# serial-io.net
KiCad netlist of a schematic drawn in Altium Designer
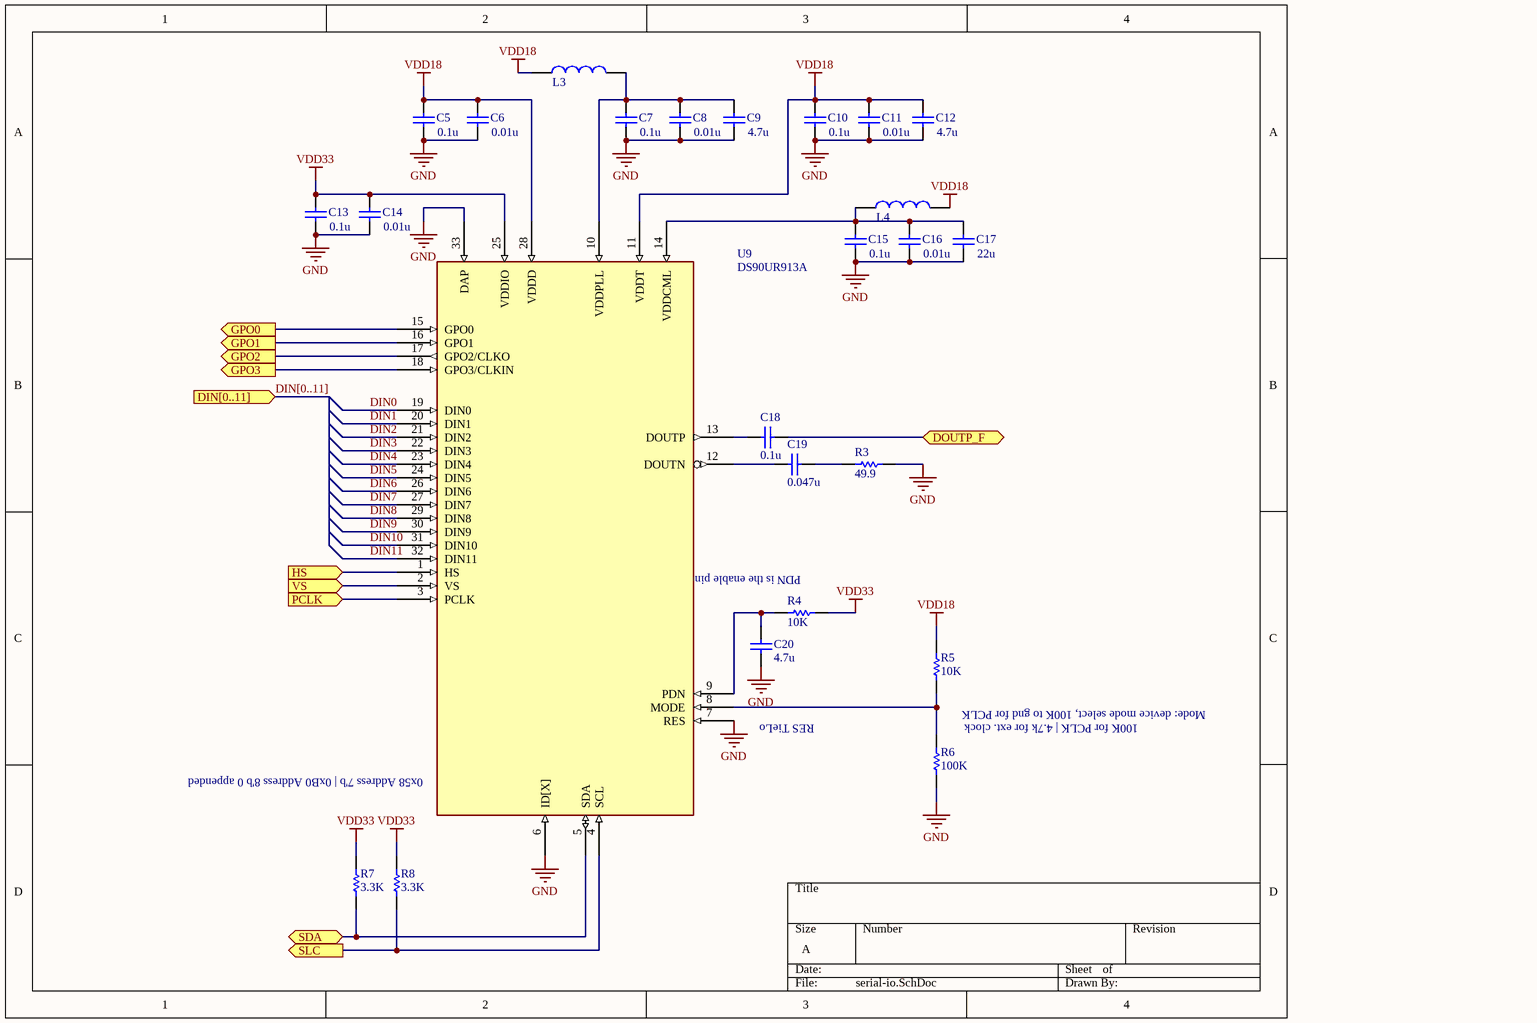
[diagram p0: serial-io.SchDoc]

(export (version "E")
  (design (tool "Eeschema 10.0.6"))
  (components
    (comp (ref "C5")
      (value "0.1u")
      (footprint "Cap_0402")
      (description "Capacitor")
      (fields (field (name "Comment") "X7R Ceramic") (field (name "PUBLISHER") "Altium Limited"))
      (libsource (lib "Miscellaneous Devices") (part "Cap"))
    )
    (comp (ref "C6")
      (value "0.01u")
      (footprint "Cap_0402")
      (description "Capacitor")
      (fields (field (name "Comment") "X7R Ceramic") (field (name "PUBLISHER") "Altium Limited"))
      (libsource (lib "Miscellaneous Devices") (part "Cap"))
    )
    (comp (ref "C7")
      (value "0.1u")
      (footprint "Cap_0402")
      (description "Capacitor")
      (fields (field (name "Comment") "X7R Ceramic") (field (name "PUBLISHER") "Altium Limited"))
      (libsource (lib "Miscellaneous Devices") (part "Cap"))
    )
    (comp (ref "C8")
      (value "0.01u")
      (footprint "Cap_0402")
      (description "Capacitor")
      (fields (field (name "Comment") "X7R Ceramic") (field (name "PUBLISHER") "Altium Limited"))
      (libsource (lib "Miscellaneous Devices") (part "Cap"))
    )
    (comp (ref "C9")
      (value "4.7u")
      (footprint "Cap_0402")
      (description "Capacitor")
      (fields (field (name "Comment") "X7R Ceramic") (field (name "PUBLISHER") "Altium Limited"))
      (libsource (lib "Miscellaneous Devices") (part "Cap"))
    )
    (comp (ref "C10")
      (value "0.1u")
      (footprint "Cap_0402")
      (description "Capacitor")
      (fields (field (name "Comment") "X7R Ceramic") (field (name "PUBLISHER") "Altium Limited"))
      (libsource (lib "Miscellaneous Devices") (part "Cap"))
    )
    (comp (ref "C11")
      (value "0.01u")
      (footprint "Cap_0402")
      (description "Capacitor")
      (fields (field (name "Comment") "X7R Ceramic") (field (name "PUBLISHER") "Altium Limited"))
      (libsource (lib "Miscellaneous Devices") (part "Cap"))
    )
    (comp (ref "C12")
      (value "4.7u")
      (footprint "Cap_0402")
      (description "Capacitor")
      (fields (field (name "Comment") "X7R Ceramic") (field (name "PUBLISHER") "Altium Limited"))
      (libsource (lib "Miscellaneous Devices") (part "Cap"))
    )
    (comp (ref "C13")
      (value "0.1u")
      (footprint "Cap_0402")
      (description "Capacitor")
      (fields (field (name "Comment") "X7R Ceramic") (field (name "PUBLISHER") "Altium Limited"))
      (libsource (lib "Miscellaneous Devices") (part "Cap"))
    )
    (comp (ref "C14")
      (value "0.01u")
      (footprint "Cap_0402")
      (description "Capacitor")
      (fields (field (name "Comment") "X7R Ceramic") (field (name "PUBLISHER") "Altium Limited"))
      (libsource (lib "Miscellaneous Devices") (part "Cap"))
    )
    (comp (ref "C15")
      (value "0.1u")
      (footprint "Cap_0402")
      (description "Capacitor")
      (fields (field (name "Comment") "X7R Ceramic") (field (name "PUBLISHER") "Altium Limited"))
      (libsource (lib "Miscellaneous Devices") (part "Cap"))
    )
    (comp (ref "C16")
      (value "0.01u")
      (footprint "Cap_0402")
      (description "Capacitor")
      (fields (field (name "Comment") "X7R Ceramic") (field (name "PUBLISHER") "Altium Limited"))
      (libsource (lib "Miscellaneous Devices") (part "Cap"))
    )
    (comp (ref "C17")
      (value "22u")
      (footprint "Cap-0603")
      (description "Capacitor")
      (fields (field (name "Comment") "X7R Ceramic") (field (name "PUBLISHER") "Altium Limited"))
      (libsource (lib "Miscellaneous Devices") (part "Cap"))
    )
    (comp (ref "C18")
      (value "0.1u")
      (footprint "Cap_0402")
      (description "Capacitor")
      (fields (field (name "Comment") "X7R Ceramic") (field (name "PUBLISHER") "Altium Limited"))
      (libsource (lib "Miscellaneous Devices") (part "Cap"))
    )
    (comp (ref "C19")
      (value "0.047u")
      (footprint "Cap_0402")
      (description "Capacitor")
      (fields (field (name "Comment") "X7R Ceramic") (field (name "PUBLISHER") "Altium Limited"))
      (libsource (lib "Miscellaneous Devices") (part "Cap"))
    )
    (comp (ref "C20")
      (value "4.7u")
      (footprint "Cap_0402")
      (description "Capacitor")
      (fields (field (name "Comment") "X7R Ceramic") (field (name "PUBLISHER") "Altium Limited"))
      (libsource (lib "Miscellaneous Devices") (part "Cap"))
    )
    (comp (ref "L3")
      (value "Ferrite Bead")
      (footprint "BLM18KG601SN1D")
      (libsource (lib "DA_Component_Library") (part "Ferrite Bead"))
    )
    (comp (ref "L4")
      (value "Ferrite Bead")
      (footprint "BLM18KG601SN1D")
      (libsource (lib "DA_Component_Library") (part "Ferrite Bead"))
    )
    (comp (ref "R3")
      (value "49.9")
      (footprint "Res_0402")
      (description "Resistor")
      (fields (field (name "Comment") "Res1") (field (name "PUBLISHER") "Altium Limited"))
      (libsource (lib "Miscellaneous Devices") (part "Res1"))
    )
    (comp (ref "R4")
      (value "10K")
      (footprint "Res_0402")
      (description "Resistor")
      (fields (field (name "Comment") "Res1") (field (name "PUBLISHER") "Altium Limited"))
      (libsource (lib "Miscellaneous Devices") (part "Res1"))
    )
    (comp (ref "R5")
      (value "10K")
      (footprint "Res_0402")
      (description "Resistor")
      (fields (field (name "Comment") "Res1") (field (name "PUBLISHER") "Altium Limited"))
      (libsource (lib "Miscellaneous Devices") (part "Res1"))
    )
    (comp (ref "R6")
      (value "100K")
      (footprint "Res_0402")
      (description "Resistor")
      (fields (field (name "Comment") "Res1") (field (name "PUBLISHER") "Altium Limited"))
      (libsource (lib "Miscellaneous Devices") (part "Res1"))
    )
    (comp (ref "R7")
      (value "3.3K")
      (footprint "Res_0402")
      (description "Resistor")
      (fields (field (name "Comment") "Res1") (field (name "PUBLISHER") "Altium Limited"))
      (libsource (lib "Miscellaneous Devices") (part "Res1"))
    )
    (comp (ref "R8")
      (value "3.3K")
      (footprint "Res_0402")
      (description "Resistor")
      (fields (field (name "Comment") "Res1") (field (name "PUBLISHER") "Altium Limited"))
      (libsource (lib "Miscellaneous Devices") (part "Res1"))
    )
    (comp (ref "U9")
      (value "DS90UR913A")
      (footprint "WQFN32-DS90UB913A")
      (description "DS90UR913ASERIALIZER")
      (libsource (lib "DA_Component_Library") (part "DS90UR913A"))
    )
  )
  (nets
    (net (code "1") (name "/DIN0") (class "Default")
      (node (ref "U9") (pin "19") (pinfunction "DIN0_19") (pintype "input"))
    )
    (net (code "2") (name "/DIN1") (class "Default")
      (node (ref "U9") (pin "20") (pinfunction "DIN1_20") (pintype "input"))
    )
    (net (code "3") (name "/DIN2") (class "Default")
      (node (ref "U9") (pin "21") (pinfunction "DIN2_21") (pintype "input"))
    )
    (net (code "4") (name "/DIN3") (class "Default")
      (node (ref "U9") (pin "22") (pinfunction "DIN3_22") (pintype "input"))
    )
    (net (code "5") (name "/DIN4") (class "Default")
      (node (ref "U9") (pin "23") (pinfunction "DIN4_23") (pintype "input"))
    )
    (net (code "6") (name "/DIN5") (class "Default")
      (node (ref "U9") (pin "24") (pinfunction "DIN5_24") (pintype "input"))
    )
    (net (code "7") (name "/DIN6") (class "Default")
      (node (ref "U9") (pin "26") (pinfunction "DIN6_26") (pintype "input"))
    )
    (net (code "8") (name "/DIN7") (class "Default")
      (node (ref "U9") (pin "27") (pinfunction "DIN7_27") (pintype "input"))
    )
    (net (code "9") (name "/DIN8") (class "Default")
      (node (ref "U9") (pin "29") (pinfunction "DIN8_29") (pintype "input"))
    )
    (net (code "10") (name "/DIN9") (class "Default")
      (node (ref "U9") (pin "30") (pinfunction "DIN9_30") (pintype "input"))
    )
    (net (code "11") (name "/DIN10") (class "Default")
      (node (ref "U9") (pin "31") (pinfunction "DIN10_31") (pintype "input"))
    )
    (net (code "12") (name "/DIN11") (class "Default")
      (node (ref "U9") (pin "32") (pinfunction "DIN11_32") (pintype "input"))
    )
    (net (code "14") (name "/DOUTP_F") (class "Default")
      (node (ref "C18") (pin "1") (pinfunction "1_1") (pintype "passive"))
    )
    (net (code "15") (name "/GPO0") (class "Default")
      (node (ref "U9") (pin "15") (pinfunction "GPO0_15") (pintype "input"))
    )
    (net (code "16") (name "/GPO1") (class "Default")
      (node (ref "U9") (pin "16") (pinfunction "GPO1_16") (pintype "input"))
    )
    (net (code "17") (name "/GPO2") (class "Default")
      (node (ref "U9") (pin "17") (pinfunction "GPO2/CLKO_17") (pintype "output"))
    )
    (net (code "18") (name "/GPO3") (class "Default")
      (node (ref "U9") (pin "18") (pinfunction "GPO3/CLKIN_18") (pintype "input"))
    )
    (net (code "19") (name "/HS") (class "Default")
      (node (ref "U9") (pin "1") (pinfunction "HS_1") (pintype "input"))
    )
    (net (code "20") (name "/PCLK") (class "Default")
      (node (ref "U9") (pin "3") (pinfunction "PCLK_3") (pintype "input"))
    )
    (net (code "21") (name "/SDA") (class "Default")
      (node (ref "R7") (pin "1") (pinfunction "1_1") (pintype "passive"))
      (node (ref "U9") (pin "5") (pinfunction "SDA_5") (pintype "bidirectional"))
    )
    (net (code "22") (name "/SLC") (class "Default")
      (node (ref "R8") (pin "1") (pinfunction "1_1") (pintype "passive"))
      (node (ref "U9") (pin "4") (pinfunction "SCL_4") (pintype "input"))
    )
    (net (code "23") (name "/VS") (class "Default")
      (node (ref "U9") (pin "2") (pinfunction "VS_2") (pintype "input"))
    )
    (net (code "24") (name "GND") (class "Default")
      (node (ref "C10") (pin "1") (pinfunction "1_1") (pintype "passive"))
      (node (ref "C11") (pin "1") (pinfunction "1_1") (pintype "passive"))
      (node (ref "C12") (pin "1") (pinfunction "1_1") (pintype "passive"))
      (node (ref "C13") (pin "1") (pinfunction "1_1") (pintype "passive"))
      (node (ref "C14") (pin "1") (pinfunction "1_1") (pintype "passive"))
      (node (ref "C15") (pin "1") (pinfunction "1_1") (pintype "passive"))
      (node (ref "C16") (pin "1") (pinfunction "1_1") (pintype "passive"))
      (node (ref "C17") (pin "1") (pinfunction "1_1") (pintype "passive"))
      (node (ref "C20") (pin "1") (pinfunction "1_1") (pintype "passive"))
      (node (ref "C5") (pin "1") (pinfunction "1_1") (pintype "passive"))
      (node (ref "C6") (pin "1") (pinfunction "1_1") (pintype "passive"))
      (node (ref "C7") (pin "1") (pinfunction "1_1") (pintype "passive"))
      (node (ref "C8") (pin "1") (pinfunction "1_1") (pintype "passive"))
      (node (ref "C9") (pin "1") (pinfunction "1_1") (pintype "passive"))
      (node (ref "R3") (pin "2") (pinfunction "2_2") (pintype "passive"))
      (node (ref "R6") (pin "1") (pinfunction "1_1") (pintype "passive"))
      (node (ref "U9") (pin "33") (pinfunction "DAP_33") (pintype "input"))
      (node (ref "U9") (pin "6") (pinfunction "ID[X]_6") (pintype "input"))
      (node (ref "U9") (pin "7") (pinfunction "RES_7") (pintype "input"))
    )
    (net (code "25") (name "Net-(C19-Pad1)") (class "Default")
      (node (ref "C19") (pin "1") (pinfunction "1_1") (pintype "passive"))
      (node (ref "R3") (pin "1") (pinfunction "1_1") (pintype "passive"))
    )
    (net (code "26") (name "Net-(U9-DOUTN)") (class "Default")
      (node (ref "C19") (pin "2") (pinfunction "2_2") (pintype "passive"))
      (node (ref "U9") (pin "12") (pinfunction "DOUTN_12") (pintype "output"))
    )
    (net (code "27") (name "Net-(U9-DOUTP)") (class "Default")
      (node (ref "C18") (pin "2") (pinfunction "2_2") (pintype "passive"))
      (node (ref "U9") (pin "13") (pinfunction "DOUTP_13") (pintype "output"))
    )
    (net (code "28") (name "Net-(U9-MODE)") (class "Default")
      (node (ref "R5") (pin "1") (pinfunction "1_1") (pintype "passive"))
      (node (ref "R6") (pin "2") (pinfunction "2_2") (pintype "passive"))
      (node (ref "U9") (pin "8") (pinfunction "MODE_8") (pintype "input"))
    )
    (net (code "29") (name "Net-(U9-PDN)") (class "Default")
      (node (ref "C20") (pin "2") (pinfunction "2_2") (pintype "passive"))
      (node (ref "R4") (pin "1") (pinfunction "1_1") (pintype "passive"))
      (node (ref "U9") (pin "9") (pinfunction "PDN_9") (pintype "input"))
    )
    (net (code "30") (name "Net-(U9-VDDCML)") (class "Default")
      (node (ref "C15") (pin "2") (pinfunction "2_2") (pintype "passive"))
      (node (ref "C16") (pin "2") (pinfunction "2_2") (pintype "passive"))
      (node (ref "C17") (pin "2") (pinfunction "2_2") (pintype "passive"))
      (node (ref "L4") (pin "1") (pinfunction "1_1") (pintype "passive"))
      (node (ref "U9") (pin "14") (pinfunction "VDDCML_14") (pintype "input"))
    )
    (net (code "31") (name "Net-(U9-VDDPLL)") (class "Default")
      (node (ref "C7") (pin "2") (pinfunction "2_2") (pintype "passive"))
      (node (ref "C8") (pin "2") (pinfunction "2_2") (pintype "passive"))
      (node (ref "C9") (pin "2") (pinfunction "2_2") (pintype "passive"))
      (node (ref "L3") (pin "2") (pinfunction "2_2") (pintype "passive"))
      (node (ref "U9") (pin "10") (pinfunction "VDDPLL_10") (pintype "input"))
    )
    (net (code "32") (name "VDD18") (class "Default")
      (node (ref "C10") (pin "2") (pinfunction "2_2") (pintype "passive"))
      (node (ref "C11") (pin "2") (pinfunction "2_2") (pintype "passive"))
      (node (ref "C12") (pin "2") (pinfunction "2_2") (pintype "passive"))
      (node (ref "C5") (pin "2") (pinfunction "2_2") (pintype "passive"))
      (node (ref "C6") (pin "2") (pinfunction "2_2") (pintype "passive"))
      (node (ref "L3") (pin "1") (pinfunction "1_1") (pintype "passive"))
      (node (ref "L4") (pin "2") (pinfunction "2_2") (pintype "passive"))
      (node (ref "R5") (pin "2") (pinfunction "2_2") (pintype "passive"))
      (node (ref "U9") (pin "11") (pinfunction "VDDT_11") (pintype "input"))
      (node (ref "U9") (pin "28") (pinfunction "VDDD_28") (pintype "input"))
    )
    (net (code "33") (name "VDD33") (class "Default")
      (node (ref "C13") (pin "2") (pinfunction "2_2") (pintype "passive"))
      (node (ref "C14") (pin "2") (pinfunction "2_2") (pintype "passive"))
      (node (ref "R4") (pin "2") (pinfunction "2_2") (pintype "passive"))
      (node (ref "R7") (pin "2") (pinfunction "2_2") (pintype "passive"))
      (node (ref "R8") (pin "2") (pinfunction "2_2") (pintype "passive"))
      (node (ref "U9") (pin "25") (pinfunction "VDDIO_25") (pintype "input"))
    )
  )
)
